# 04_MICROCONTROLLER.net
KiCad netlist of a schematic drawn in Altium Designer
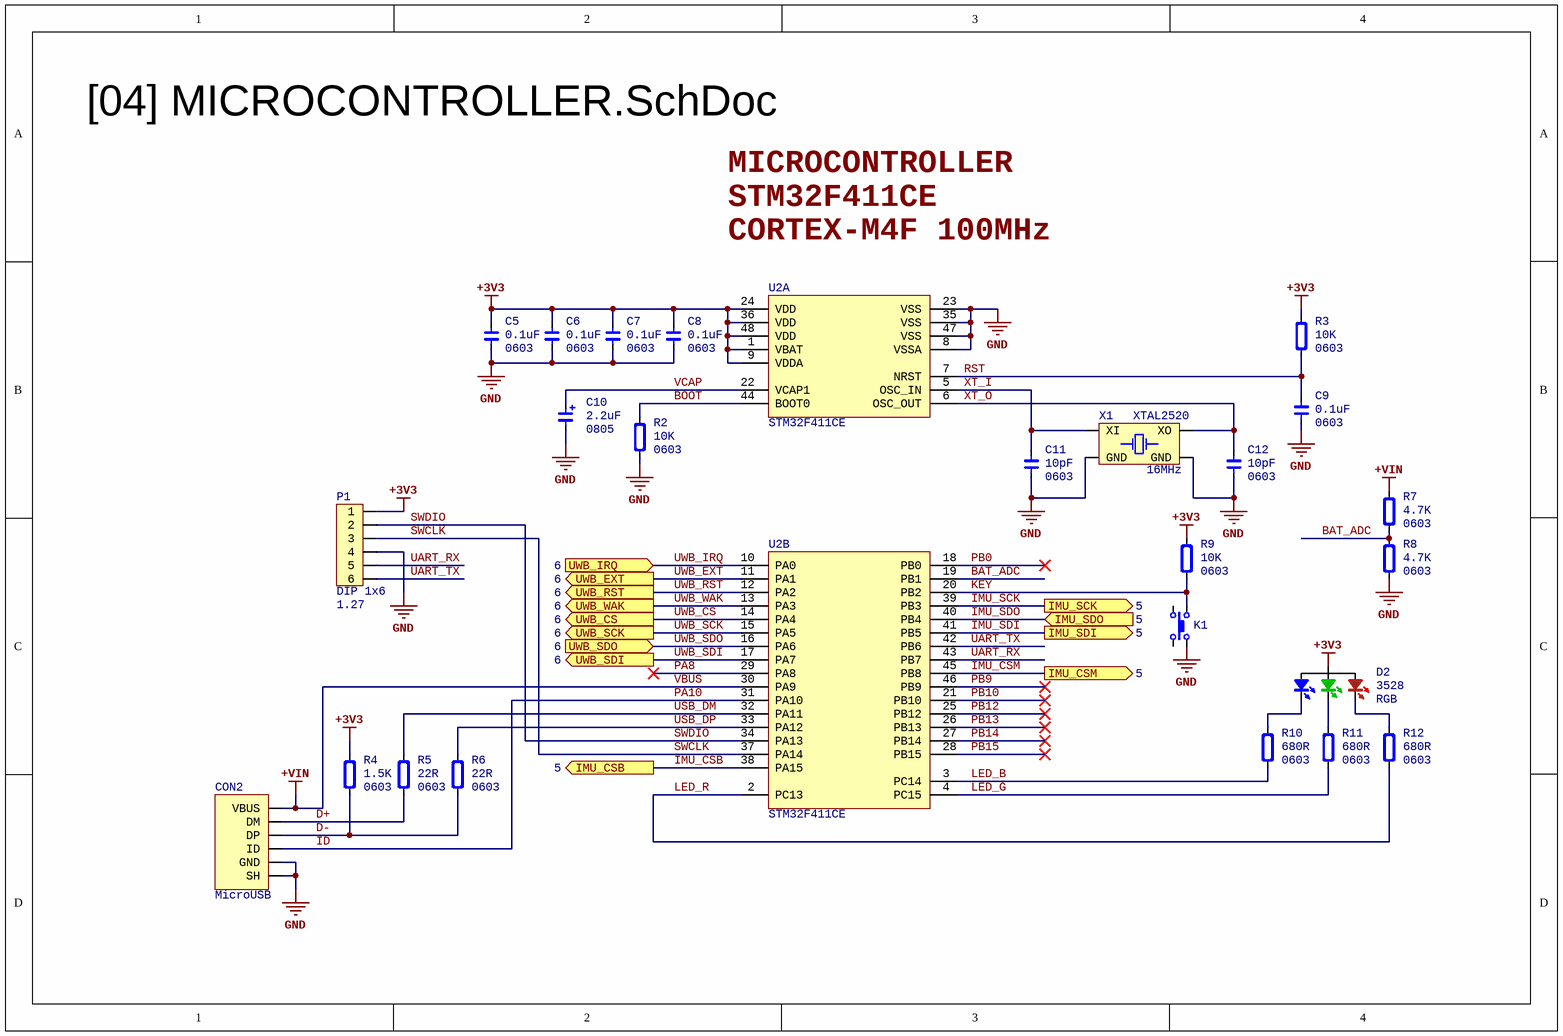
[diagram p0: [04] MICROCONTROLLER.SchDoc]

(export (version "E")
  (design (tool "Eeschema 10.0.6"))
  (components
    (comp (ref "C5")
      (value "0.1uF")
      (footprint "PCB_PassiveCap:CAP_0603")
      (description "Capacitor")
      (fields (field (name "TYPE") "0603"))
      (libsource (lib "SCH_Passive") (part "Cap_0603"))
    )
    (comp (ref "C6")
      (value "0.1uF")
      (footprint "PCB_PassiveCap:CAP_0603")
      (description "Capacitor")
      (fields (field (name "TYPE") "0603"))
      (libsource (lib "SCH_Passive") (part "Cap_0603"))
    )
    (comp (ref "C7")
      (value "0.1uF")
      (footprint "PCB_PassiveCap:CAP_0603")
      (description "Capacitor")
      (fields (field (name "TYPE") "0603"))
      (libsource (lib "SCH_Passive") (part "Cap_0603"))
    )
    (comp (ref "C8")
      (value "0.1uF")
      (footprint "PCB_PassiveCap:CAP_0603")
      (description "Capacitor")
      (fields (field (name "TYPE") "0603"))
      (libsource (lib "SCH_Passive") (part "Cap_0603"))
    )
    (comp (ref "C9")
      (value "0.1uF")
      (footprint "PCB_PassiveCap:CAP_0603")
      (description "Capacitor")
      (fields (field (name "TYPE") "0603"))
      (libsource (lib "SCH_Passive") (part "Cap_0603"))
    )
    (comp (ref "C10")
      (value "2.2uF")
      (footprint "PCB_PassiveCap:CAP_TAN_P0805")
      (description "Capacitor Tantalum")
      (fields (field (name "TYPE") "0805"))
      (libsource (lib "SCH_Passive") (part "Cap_Tan_0805"))
    )
    (comp (ref "C11")
      (value "10pF")
      (footprint "PCB_PassiveCap:CAP_0603")
      (description "Capacitor")
      (fields (field (name "TYPE") "0603"))
      (libsource (lib "SCH_Passive") (part "Cap_0603"))
    )
    (comp (ref "C12")
      (value "10pF")
      (footprint "PCB_PassiveCap:CAP_0603")
      (description "Capacitor")
      (fields (field (name "TYPE") "0603"))
      (libsource (lib "SCH_Passive") (part "Cap_0603"))
    )
    (comp (ref "CON2")
      (value "MicroUSB")
      (footprint "PCB_USB:USB_Micro-AB")
      (description "USB")
      (libsource (lib "SCH_USB") (part "USB_Micro"))
    )
    (comp (ref "D2")
      (value "RGB")
      (footprint "PCB_ActiveLED:LED_3528_RGB")
      (description "LED")
      (fields (field (name "TYPE") "3528"))
      (libsource (lib "SCH_Active") (part "LED_3528_RGB"))
    )
    (comp (ref "K1")
      (value "ButtonTACT")
      (footprint "PCB_Switch:ButtonTACT_3.4*3.5_90")
      (description "Button")
      (libsource (lib "SCH_Switch") (part "ButtonTACT"))
    )
    (comp (ref "P1")
      (value "1.27")
      (footprint "PCB_ConnectorHDR:HDR1X6_1.27_180HF")
      (description "Header")
      (fields (field (name "TYPE") "DIP 1x6") (field (name "Comment") "DIP 1x6"))
      (libsource (lib "SCH_ConnectorHDR") (part "HDR1x6_1.27T"))
    )
    (comp (ref "R2")
      (value "10K")
      (footprint "PCB_PassiveRes:RES_0603")
      (description "Resistor")
      (fields (field (name "TYPE") "0603"))
      (libsource (lib "SCH_Passive") (part "Res_0603"))
    )
    (comp (ref "R3")
      (value "10K")
      (footprint "PCB_PassiveRes:RES_0603")
      (description "Resistor")
      (fields (field (name "TYPE") "0603"))
      (libsource (lib "SCH_Passive") (part "Res_0603"))
    )
    (comp (ref "R4")
      (value "1.5K")
      (footprint "PCB_PassiveRes:RES_0603")
      (description "Resistor")
      (fields (field (name "TYPE") "0603"))
      (libsource (lib "SCH_Passive") (part "Res_0603"))
    )
    (comp (ref "R5")
      (value "22R")
      (footprint "PCB_PassiveRes:RES_0603")
      (description "Resistor")
      (fields (field (name "TYPE") "0603"))
      (libsource (lib "SCH_Passive") (part "Res_0603"))
    )
    (comp (ref "R6")
      (value "22R")
      (footprint "PCB_PassiveRes:RES_0603")
      (description "Resistor")
      (fields (field (name "TYPE") "0603"))
      (libsource (lib "SCH_Passive") (part "Res_0603"))
    )
    (comp (ref "R7")
      (value "4.7K")
      (footprint "PCB_PassiveRes:RES_0603")
      (description "Resistor")
      (fields (field (name "TYPE") "0603"))
      (libsource (lib "SCH_Passive") (part "Res_0603"))
    )
    (comp (ref "R8")
      (value "4.7K")
      (footprint "PCB_PassiveRes:RES_0603")
      (description "Resistor")
      (fields (field (name "TYPE") "0603"))
      (libsource (lib "SCH_Passive") (part "Res_0603"))
    )
    (comp (ref "R9")
      (value "10K")
      (footprint "PCB_PassiveRes:RES_0603")
      (description "Resistor")
      (fields (field (name "TYPE") "0603"))
      (libsource (lib "SCH_Passive") (part "Res_0603"))
    )
    (comp (ref "R10")
      (value "680R")
      (footprint "PCB_PassiveRes:RES_0603")
      (description "Resistor")
      (fields (field (name "TYPE") "0603"))
      (libsource (lib "SCH_Passive") (part "Res_0603"))
    )
    (comp (ref "R11")
      (value "680R")
      (footprint "PCB_PassiveRes:RES_0603")
      (description "Resistor")
      (fields (field (name "TYPE") "0603"))
      (libsource (lib "SCH_Passive") (part "Res_0603"))
    )
    (comp (ref "R12")
      (value "680R")
      (footprint "PCB_PassiveRes:RES_0603")
      (description "Resistor")
      (fields (field (name "TYPE") "0603"))
      (libsource (lib "SCH_Passive") (part "Res_0603"))
    )
    (comp (ref "U2")
      (value "STM32F411CE")
      (footprint "PCB_IntegratedCircuit:QFN_P0.5_48")
      (description "MCU")
      (libsource (lib "SCH_IntegratedCircuit") (part "STM32F4x1C"))
    )
    (comp (ref "X1")
      (value "16MHz")
      (footprint "PCB_Oscillator:XT_2520_4")
      (description "Crystal Oscillator")
      (fields (field (name "TYPE") "XTAL2520"))
      (libsource (lib "SCH_Oscillator") (part "XTAL_2520_4P"))
    )
  )
  (nets
    (net (code "1") (name "+3V3") (class "Default")
      (node (ref "C5") (pin "2") (pinfunction "2_2") (pintype "passive"))
      (node (ref "C6") (pin "2") (pinfunction "2_2") (pintype "passive"))
      (node (ref "C7") (pin "2") (pinfunction "2_2") (pintype "passive"))
      (node (ref "C8") (pin "2") (pinfunction "2_2") (pintype "passive"))
      (node (ref "D2") (pin "4") (pinfunction "A_4") (pintype "passive"))
      (node (ref "P1") (pin "1") (pinfunction "1_1") (pintype "passive"))
      (node (ref "R3") (pin "2") (pinfunction "2_2") (pintype "passive"))
      (node (ref "R4") (pin "2") (pinfunction "2_2") (pintype "passive"))
      (node (ref "R9") (pin "2") (pinfunction "2_2") (pintype "passive"))
      (node (ref "U2") (pin "1") (pinfunction "VBAT_1") (pintype "passive"))
      (node (ref "U2") (pin "24") (pinfunction "VDD_24") (pintype "passive"))
      (node (ref "U2") (pin "36") (pinfunction "VDD_36") (pintype "passive"))
      (node (ref "U2") (pin "48") (pinfunction "VDD_48") (pintype "passive"))
      (node (ref "U2") (pin "9") (pinfunction "VDDA_9") (pintype "passive"))
    )
    (net (code "2") (name "+VIN") (class "Default")
      (node (ref "CON2") (pin "1") (pinfunction "VBUS_1") (pintype "passive"))
      (node (ref "R7") (pin "2") (pinfunction "2_2") (pintype "passive"))
      (node (ref "U2") (pin "30") (pinfunction "PA9_30") (pintype "passive"))
    )
    (net (code "3") (name "/BAT_ADC") (class "Default")
      (node (ref "R7") (pin "1") (pinfunction "1_1") (pintype "passive"))
      (node (ref "R8") (pin "2") (pinfunction "2_2") (pintype "passive"))
      (node (ref "U2") (pin "19") (pinfunction "PB1_19") (pintype "passive"))
    )
    (net (code "4") (name "/BOOT") (class "Default")
      (node (ref "R2") (pin "2") (pinfunction "2_2") (pintype "passive"))
      (node (ref "U2") (pin "44") (pinfunction "BOOT0_44") (pintype "passive"))
    )
    (net (code "5") (name "/D+") (class "Default")
      (node (ref "CON2") (pin "2") (pinfunction "DM_2") (pintype "passive"))
      (node (ref "R5") (pin "1") (pinfunction "1_1") (pintype "passive"))
    )
    (net (code "6") (name "/D-") (class "Default")
      (node (ref "CON2") (pin "3") (pinfunction "DP_3") (pintype "passive"))
      (node (ref "R4") (pin "1") (pinfunction "1_1") (pintype "passive"))
      (node (ref "R6") (pin "1") (pinfunction "1_1") (pintype "passive"))
    )
    (net (code "7") (name "/ID") (class "Default")
      (node (ref "CON2") (pin "4") (pinfunction "ID_4") (pintype "passive"))
      (node (ref "U2") (pin "31") (pinfunction "PA10_31") (pintype "passive"))
    )
    (net (code "8") (name "/IMU_CSB") (class "Default")
      (node (ref "U2") (pin "38") (pinfunction "PA15_38") (pintype "passive"))
    )
    (net (code "9") (name "/IMU_CSM") (class "Default")
      (node (ref "U2") (pin "45") (pinfunction "PB8_45") (pintype "passive"))
    )
    (net (code "10") (name "/IMU_SCK") (class "Default")
      (node (ref "U2") (pin "39") (pinfunction "PB3_39") (pintype "passive"))
    )
    (net (code "11") (name "/IMU_SDI") (class "Default")
      (node (ref "U2") (pin "41") (pinfunction "PB5_41") (pintype "passive"))
    )
    (net (code "12") (name "/IMU_SDO") (class "Default")
      (node (ref "U2") (pin "40") (pinfunction "PB4_40") (pintype "passive"))
    )
    (net (code "13") (name "/KEY") (class "Default")
      (node (ref "K1") (pin "1") (pinfunction "1_1") (pintype "passive"))
      (node (ref "R9") (pin "1") (pinfunction "1_1") (pintype "passive"))
      (node (ref "U2") (pin "20") (pinfunction "PB2_20") (pintype "passive"))
    )
    (net (code "14") (name "/LED_B") (class "Default")
      (node (ref "R10") (pin "1") (pinfunction "1_1") (pintype "passive"))
      (node (ref "U2") (pin "3") (pinfunction "PC14_3") (pintype "passive"))
    )
    (net (code "15") (name "/LED_G") (class "Default")
      (node (ref "R11") (pin "1") (pinfunction "1_1") (pintype "passive"))
      (node (ref "U2") (pin "4") (pinfunction "PC15_4") (pintype "passive"))
    )
    (net (code "16") (name "/LED_R") (class "Default")
      (node (ref "R12") (pin "1") (pinfunction "1_1") (pintype "passive"))
      (node (ref "U2") (pin "2") (pinfunction "PC13_2") (pintype "passive"))
    )
    (net (code "17") (name "/PA8") (class "Default")
      (node (ref "U2") (pin "29") (pinfunction "PA8_29") (pintype "passive+no_connect"))
    )
    (net (code "18") (name "/PB0") (class "Default")
      (node (ref "U2") (pin "18") (pinfunction "PB0_18") (pintype "passive+no_connect"))
    )
    (net (code "19") (name "/PB9") (class "Default")
      (node (ref "U2") (pin "46") (pinfunction "PB9_46") (pintype "passive+no_connect"))
    )
    (net (code "20") (name "/PB10") (class "Default")
      (node (ref "U2") (pin "21") (pinfunction "PB10_21") (pintype "passive+no_connect"))
    )
    (net (code "21") (name "/PB12") (class "Default")
      (node (ref "U2") (pin "25") (pinfunction "PB12_25") (pintype "passive+no_connect"))
    )
    (net (code "22") (name "/PB13") (class "Default")
      (node (ref "U2") (pin "26") (pinfunction "PB13_26") (pintype "passive+no_connect"))
    )
    (net (code "23") (name "/PB14") (class "Default")
      (node (ref "U2") (pin "27") (pinfunction "PB14_27") (pintype "passive+no_connect"))
    )
    (net (code "24") (name "/PB15") (class "Default")
      (node (ref "U2") (pin "28") (pinfunction "PB15_28") (pintype "passive+no_connect"))
    )
    (net (code "25") (name "/RST") (class "Default")
      (node (ref "C9") (pin "2") (pinfunction "2_2") (pintype "passive"))
      (node (ref "R3") (pin "1") (pinfunction "1_1") (pintype "passive"))
      (node (ref "U2") (pin "7") (pinfunction "NRST_7") (pintype "passive"))
    )
    (net (code "26") (name "/SWCLK") (class "Default")
      (node (ref "P1") (pin "3") (pinfunction "3_3") (pintype "passive"))
      (node (ref "U2") (pin "37") (pinfunction "PA14_37") (pintype "passive"))
    )
    (net (code "27") (name "/SWDIO") (class "Default")
      (node (ref "P1") (pin "2") (pinfunction "2_2") (pintype "passive"))
      (node (ref "U2") (pin "34") (pinfunction "PA13_34") (pintype "passive"))
    )
    (net (code "28") (name "/UART_RX") (class "Default")
      (node (ref "P1") (pin "5") (pinfunction "5_5") (pintype "passive"))
      (node (ref "U2") (pin "43") (pinfunction "PB7_43") (pintype "passive"))
    )
    (net (code "29") (name "/UART_TX") (class "Default")
      (node (ref "P1") (pin "6") (pinfunction "6_6") (pintype "passive"))
      (node (ref "U2") (pin "42") (pinfunction "PB6_42") (pintype "passive"))
    )
    (net (code "30") (name "/USB_DM") (class "Default")
      (node (ref "R5") (pin "2") (pinfunction "2_2") (pintype "passive"))
      (node (ref "U2") (pin "32") (pinfunction "PA11_32") (pintype "passive"))
    )
    (net (code "31") (name "/USB_DP") (class "Default")
      (node (ref "R6") (pin "2") (pinfunction "2_2") (pintype "passive"))
      (node (ref "U2") (pin "33") (pinfunction "PA12_33") (pintype "passive"))
    )
    (net (code "32") (name "/UWB_CS") (class "Default")
      (node (ref "U2") (pin "14") (pinfunction "PA4_14") (pintype "passive"))
    )
    (net (code "33") (name "/UWB_EXT") (class "Default")
      (node (ref "U2") (pin "11") (pinfunction "PA1_11") (pintype "passive"))
    )
    (net (code "34") (name "/UWB_IRQ") (class "Default")
      (node (ref "U2") (pin "10") (pinfunction "PA0_10") (pintype "passive"))
    )
    (net (code "35") (name "/UWB_RST") (class "Default")
      (node (ref "U2") (pin "12") (pinfunction "PA2_12") (pintype "passive"))
    )
    (net (code "36") (name "/UWB_SCK") (class "Default")
      (node (ref "U2") (pin "15") (pinfunction "PA5_15") (pintype "passive"))
    )
    (net (code "37") (name "/UWB_SDI") (class "Default")
      (node (ref "U2") (pin "17") (pinfunction "PA7_17") (pintype "passive"))
    )
    (net (code "38") (name "/UWB_SDO") (class "Default")
      (node (ref "U2") (pin "16") (pinfunction "PA6_16") (pintype "passive"))
    )
    (net (code "39") (name "/UWB_WAK") (class "Default")
      (node (ref "U2") (pin "13") (pinfunction "PA3_13") (pintype "passive"))
    )
    (net (code "40") (name "/VCAP") (class "Default")
      (node (ref "C10") (pin "1") (pinfunction "1_1") (pintype "passive"))
      (node (ref "U2") (pin "22") (pinfunction "VCAP1_22") (pintype "passive"))
    )
    (net (code "41") (name "/XT_I") (class "Default")
      (node (ref "C11") (pin "2") (pinfunction "2_2") (pintype "passive"))
      (node (ref "U2") (pin "5") (pinfunction "OSC_IN_5") (pintype "passive"))
      (node (ref "X1") (pin "1") (pinfunction "XI_1") (pintype "passive"))
    )
    (net (code "42") (name "/XT_O") (class "Default")
      (node (ref "C12") (pin "2") (pinfunction "2_2") (pintype "passive"))
      (node (ref "U2") (pin "6") (pinfunction "OSC_OUT_6") (pintype "passive"))
      (node (ref "X1") (pin "3") (pinfunction "XO_3") (pintype "passive"))
    )
    (net (code "43") (name "GND") (class "Default")
      (node (ref "C10") (pin "2") (pinfunction "2_2") (pintype "passive"))
      (node (ref "C11") (pin "1") (pinfunction "1_1") (pintype "passive"))
      (node (ref "C12") (pin "1") (pinfunction "1_1") (pintype "passive"))
      (node (ref "C5") (pin "1") (pinfunction "1_1") (pintype "passive"))
      (node (ref "C6") (pin "1") (pinfunction "1_1") (pintype "passive"))
      (node (ref "C7") (pin "1") (pinfunction "1_1") (pintype "passive"))
      (node (ref "C8") (pin "1") (pinfunction "1_1") (pintype "passive"))
      (node (ref "C9") (pin "1") (pinfunction "1_1") (pintype "passive"))
      (node (ref "CON2") (pin "0") (pinfunction "SH_0") (pintype "passive"))
      (node (ref "CON2") (pin "5") (pinfunction "GND_5") (pintype "passive"))
      (node (ref "K1") (pin "2") (pinfunction "2_2") (pintype "passive"))
      (node (ref "P1") (pin "4") (pinfunction "4_4") (pintype "passive"))
      (node (ref "R2") (pin "1") (pinfunction "1_1") (pintype "passive"))
      (node (ref "R8") (pin "1") (pinfunction "1_1") (pintype "passive"))
      (node (ref "U2") (pin "23") (pinfunction "VSS_23") (pintype "passive"))
      (node (ref "U2") (pin "35") (pinfunction "VSS_35") (pintype "passive"))
      (node (ref "U2") (pin "47") (pinfunction "VSS_47") (pintype "passive"))
      (node (ref "U2") (pin "8") (pinfunction "VSSA_8") (pintype "passive"))
      (node (ref "X1") (pin "2") (pinfunction "GND_2") (pintype "passive"))
      (node (ref "X1") (pin "4") (pinfunction "GND_4") (pintype "passive"))
    )
    (net (code "44") (name "Net-(D2-B)") (class "Default")
      (node (ref "D2") (pin "3") (pinfunction "B_3") (pintype "passive"))
      (node (ref "R10") (pin "2") (pinfunction "2_2") (pintype "passive"))
    )
    (net (code "45") (name "Net-(D2-G)") (class "Default")
      (node (ref "D2") (pin "2") (pinfunction "G_2") (pintype "passive"))
      (node (ref "R11") (pin "2") (pinfunction "2_2") (pintype "passive"))
    )
    (net (code "46") (name "Net-(D2-R)") (class "Default")
      (node (ref "D2") (pin "1") (pinfunction "R_1") (pintype "passive"))
      (node (ref "R12") (pin "2") (pinfunction "2_2") (pintype "passive"))
    )
    (net (code "47") (name "unconnected-(K1-Pad3)") (class "Default")
      (node (ref "K1") (pin "3") (pinfunction "3_3") (pintype "passive"))
    )
    (net (code "48") (name "unconnected-(K1-Pad4)") (class "Default")
      (node (ref "K1") (pin "4") (pinfunction "4_4") (pintype "passive"))
    )
  )
)
